# neuron_v3.net
KiCad netlist of a schematic drawn in EAGLE
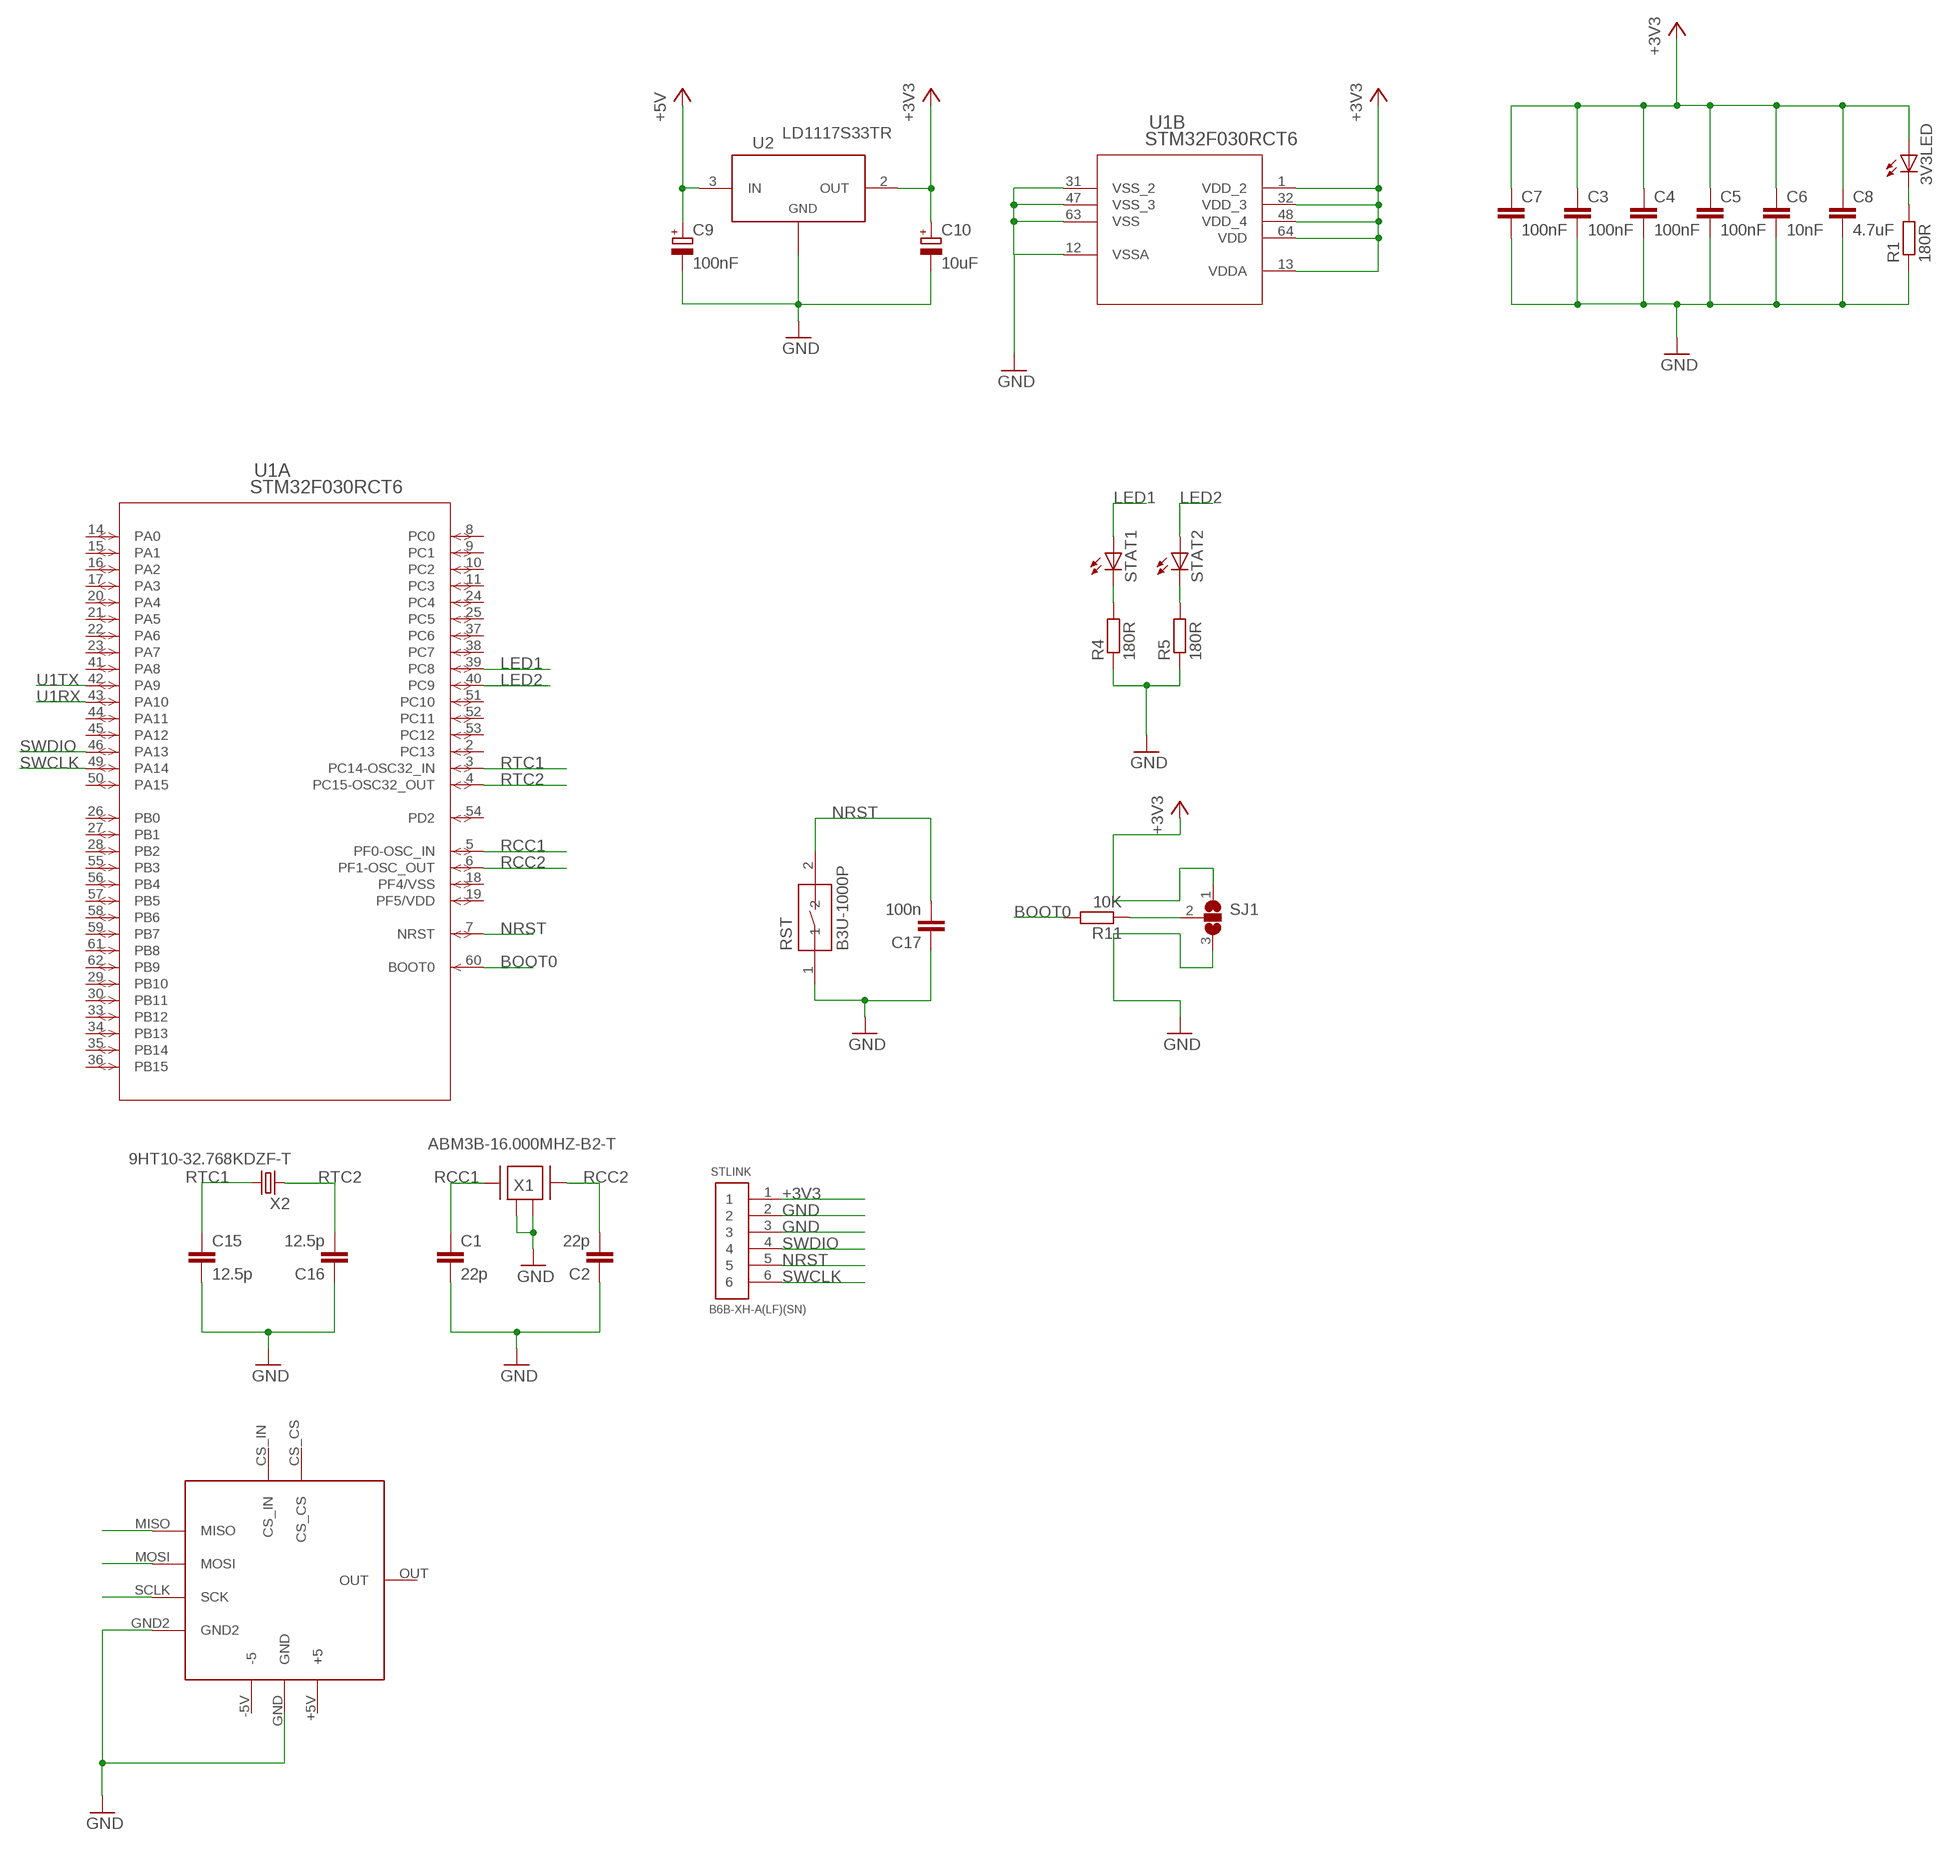
[diagram p0: schematic, sheet 1]

(export (version "E")
  (design (tool "Eeschema 10.0.6"))
  (components
    (comp (ref "3V3LED")
      (value "LEDCHIPLED_0805")
      (footprint "eagle-import:CHIPLED_0805")
      (libsource (lib "eagle-import") (part "LEDCHIPLED_0805"))
    )
    (comp (ref "C1")
      (value "22p")
      (footprint "eagle-import:C0603K")
      (libsource (lib "eagle-import") (part "C-EUC0603K"))
    )
    (comp (ref "C2")
      (value "22p")
      (footprint "eagle-import:C0603K")
      (libsource (lib "eagle-import") (part "C-EUC0603K"))
    )
    (comp (ref "C3")
      (value "100nF")
      (footprint "eagle-import:C0603K")
      (libsource (lib "eagle-import") (part "C-EUC0603K"))
    )
    (comp (ref "C4")
      (value "100nF")
      (footprint "eagle-import:C0603K")
      (libsource (lib "eagle-import") (part "C-EUC0603K"))
    )
    (comp (ref "C5")
      (value "100nF")
      (footprint "eagle-import:C0603K")
      (libsource (lib "eagle-import") (part "C-EUC0603K"))
    )
    (comp (ref "C6")
      (value "10nF")
      (footprint "eagle-import:C0603K")
      (libsource (lib "eagle-import") (part "C-EUC0603K"))
    )
    (comp (ref "C7")
      (value "100nF")
      (footprint "eagle-import:C0603K")
      (libsource (lib "eagle-import") (part "C-EUC0603K"))
    )
    (comp (ref "C8")
      (value "4.7uF")
      (footprint "eagle-import:C0603K")
      (libsource (lib "eagle-import") (part "C-EUC0603K"))
    )
    (comp (ref "C9")
      (value "100nF")
      (footprint "eagle-import:A_3216-18W")
      (libsource (lib "eagle-import") (part "CPOL-EUA/3216-18W"))
    )
    (comp (ref "C10")
      (value "10uF")
      (footprint "eagle-import:A_3216-18W")
      (libsource (lib "eagle-import") (part "CPOL-EUA/3216-18W"))
    )
    (comp (ref "C15")
      (value "12.5p")
      (footprint "eagle-import:C0603K")
      (libsource (lib "eagle-import") (part "C-EUC0603K"))
    )
    (comp (ref "C16")
      (value "12.5p")
      (footprint "eagle-import:C0603K")
      (libsource (lib "eagle-import") (part "C-EUC0603K"))
    )
    (comp (ref "C17")
      (value "100n")
      (footprint "eagle-import:C0603K")
      (libsource (lib "eagle-import") (part "C-EUC0603K"))
    )
    (comp (ref "R1")
      (value "180R")
      (footprint "eagle-import:R0603")
      (libsource (lib "eagle-import") (part "R-EU_R0603"))
    )
    (comp (ref "R4")
      (value "180R")
      (footprint "eagle-import:R0603")
      (libsource (lib "eagle-import") (part "R-EU_R0603"))
    )
    (comp (ref "R5")
      (value "180R")
      (footprint "eagle-import:R0603")
      (libsource (lib "eagle-import") (part "R-EU_R0603"))
    )
    (comp (ref "R11")
      (value "10K")
      (footprint "eagle-import:R0603")
      (libsource (lib "eagle-import") (part "R-EU_R0603"))
    )
    (comp (ref "RST")
      (value "B3U-1000P")
      (footprint "eagle-import:B3U-1000P")
      (fields
        (field (name "DIGI_KEY_PART_NUMBER") "SW1020CT-ND")
        (field (name "MANUFACTURER") "Omron Electronics Inc-EMC Div")
        (field (name "CREATED_BY") "PCBLayout.com")
      )
      (libsource (lib "eagle-import") (part "B3U-1000P"))
    )
    (comp (ref "SJ1")
      (value "SJ2W")
      (footprint "eagle-import:SJ_2")
      (libsource (lib "eagle-import") (part "SJ2W"))
    )
    (comp (ref "STAT1")
      (value "LEDCHIPLED_0805")
      (footprint "eagle-import:CHIPLED_0805")
      (libsource (lib "eagle-import") (part "LEDCHIPLED_0805"))
    )
    (comp (ref "STAT2")
      (value "LEDCHIPLED_0805")
      (footprint "eagle-import:CHIPLED_0805")
      (libsource (lib "eagle-import") (part "LEDCHIPLED_0805"))
    )
    (comp (ref "STLINK")
      (value "B6B-XH-A(LF)(SN)")
      (footprint "eagle-import:B6B-XH-A(LF)(SN)")
      (fields
        (field (name "DIGIKEY_PARTNO") "455-2271-ND")
        (field (name "MANUFACTURER") "JST Sales America Inc.")
        (field (name "CREATED_BY") "PCBLayout.com")
      )
      (libsource (lib "eagle-import") (part "B6B-XH-A(LF)(SN)"))
    )
    (comp (ref "U$1")
      (value "NEURON_BOARD")
      (footprint "eagle-import:NEURON_BOARD")
      (libsource (lib "eagle-import") (part "NEURON_BOARD"))
    )
    (comp (ref "U1")
      (value "STM32F030RCT6")
      (footprint "eagle-import:LQFP64-10X10MM")
      (fields (field (name "COPYRIGHT") "Copyright (C) 2018 Accelerated Designs. All rights reserved"))
      (libsource (lib "eagle-import") (part "STM32F030RCT6"))
    )
    (comp (ref "U2")
      (value "LD1117S33TR")
      (footprint "eagle-import:SOT-223")
      (fields
        (field (name "DIGIKEY_PART_NUMBER") "497-1242-2-ND")
        (field (name "MANUFACTURER") "STMicroelectronics")
        (field (name "CREATED_BY") "PCBLayout.com")
      )
      (libsource (lib "eagle-import") (part "LD1117S33TR"))
    )
    (comp (ref "X1")
      (value "ABM3B-16.000MHZ-B2-T")
      (footprint "eagle-import:ABM3B-16.000MHZ-B2-T")
      (fields
        (field (name "DIGIKEY_PART_NUMBER") "535-9122-2-ND")
        (field (name "MANUFACTURER") "Abracon LLC")
        (field (name "CREATED_BY") "PCBLayout.com")
      )
      (libsource (lib "eagle-import") (part "ABM3B-16.000MHZ-B2-T"))
    )
    (comp (ref "X2")
      (value "9HT10-32.768KDZF-T")
      (footprint "eagle-import:9HT10-32.768KDZF-T")
      (fields
        (field (name "DIGIKEY_PART_NUMBER") "887-1504-2-ND")
        (field (name "MANUFACTURER") "TXC CORPORATION")
        (field (name "CREATED_BY") "PCBLayout.com")
      )
      (libsource (lib "eagle-import") (part "9HT10-32.768KDZF-T"))
    )
  )
  (nets
    (net (code "1") (name "+3V3") (class "Default")
      (node (ref "3V3LED") (pin "A") (pinfunction "A_A") (pintype "passive"))
      (node (ref "C10") (pin "+") (pinfunction "+_+") (pintype "passive"))
      (node (ref "C3") (pin "1") (pinfunction "1_1") (pintype "passive"))
      (node (ref "C4") (pin "1") (pinfunction "1_1") (pintype "passive"))
      (node (ref "C5") (pin "1") (pinfunction "1_1") (pintype "passive"))
      (node (ref "C6") (pin "1") (pinfunction "1_1") (pintype "passive"))
      (node (ref "C7") (pin "1") (pinfunction "1_1") (pintype "passive"))
      (node (ref "C8") (pin "1") (pinfunction "1_1") (pintype "passive"))
      (node (ref "SJ1") (pin "1") (pinfunction "1_1") (pintype "passive"))
      (node (ref "STLINK") (pin "1") (pinfunction "1_1") (pintype "passive"))
      (node (ref "U1") (pin "1") (pinfunction "VDD_2_1") (pintype "power_in"))
      (node (ref "U1") (pin "13") (pinfunction "VDDA_13") (pintype "power_in"))
      (node (ref "U1") (pin "32") (pinfunction "VDD_3_32") (pintype "power_in"))
      (node (ref "U1") (pin "48") (pinfunction "VDD_4_48") (pintype "power_in"))
      (node (ref "U1") (pin "64") (pinfunction "VDD_64") (pintype "power_in"))
      (node (ref "U2") (pin "2") (pinfunction "OUT_2") (pintype "output"))
      (node (ref "U2") (pin "4") (pinfunction "4_4") (pintype "passive"))
    )
    (net (code "2") (name "+5V") (class "Default")
      (node (ref "C9") (pin "+") (pinfunction "+_+") (pintype "passive"))
      (node (ref "U2") (pin "3") (pinfunction "IN_3") (pintype "input"))
    )
    (net (code "3") (name "/BOOT0") (class "Default")
      (node (ref "R11") (pin "2") (pinfunction "2_2") (pintype "passive"))
      (node (ref "U1") (pin "60") (pinfunction "BOOT0_60") (pintype "input"))
    )
    (net (code "4") (name "/LED1") (class "Default")
      (node (ref "STAT1") (pin "A") (pinfunction "A_A") (pintype "passive"))
      (node (ref "U1") (pin "39") (pinfunction "PC8_39") (pintype "bidirectional"))
    )
    (net (code "5") (name "/LED2") (class "Default")
      (node (ref "STAT2") (pin "A") (pinfunction "A_A") (pintype "passive"))
      (node (ref "U1") (pin "40") (pinfunction "PC9_40") (pintype "bidirectional"))
    )
    (net (code "6") (name "/NRST") (class "Default")
      (node (ref "C17") (pin "2") (pinfunction "2_2") (pintype "passive"))
      (node (ref "RST") (pin "2") (pinfunction "2_2") (pintype "passive"))
      (node (ref "STLINK") (pin "5") (pinfunction "5_5") (pintype "passive"))
      (node (ref "U1") (pin "7") (pinfunction "NRST_7") (pintype "bidirectional"))
    )
    (net (code "7") (name "/RCC1") (class "Default")
      (node (ref "C1") (pin "1") (pinfunction "1_1") (pintype "passive"))
      (node (ref "U1") (pin "5") (pinfunction "PF0-OSC_IN_5") (pintype "bidirectional"))
      (node (ref "X1") (pin "1") (pinfunction "1_1") (pintype "passive"))
    )
    (net (code "8") (name "/RCC2") (class "Default")
      (node (ref "C2") (pin "2") (pinfunction "2_2") (pintype "passive"))
      (node (ref "U1") (pin "6") (pinfunction "PF1-OSC_OUT_6") (pintype "bidirectional"))
      (node (ref "X1") (pin "3") (pinfunction "3_3") (pintype "passive"))
    )
    (net (code "9") (name "/RTC1") (class "Default")
      (node (ref "C15") (pin "1") (pinfunction "1_1") (pintype "passive"))
      (node (ref "U1") (pin "3") (pinfunction "PC14-OSC32_IN_3") (pintype "bidirectional"))
      (node (ref "X2") (pin "2") (pinfunction "2_2") (pintype "passive"))
    )
    (net (code "10") (name "/RTC2") (class "Default")
      (node (ref "C16") (pin "2") (pinfunction "2_2") (pintype "passive"))
      (node (ref "U1") (pin "4") (pinfunction "PC15-OSC32_OUT_4") (pintype "bidirectional"))
      (node (ref "X2") (pin "1") (pinfunction "1_1") (pintype "passive"))
    )
    (net (code "11") (name "/SWCLK") (class "Default")
      (node (ref "STLINK") (pin "6") (pinfunction "6_6") (pintype "passive"))
      (node (ref "U1") (pin "49") (pinfunction "PA14_49") (pintype "bidirectional"))
    )
    (net (code "12") (name "/SWDIO") (class "Default")
      (node (ref "STLINK") (pin "4") (pinfunction "4_4") (pintype "passive"))
      (node (ref "U1") (pin "46") (pinfunction "PA13_46") (pintype "bidirectional"))
    )
    (net (code "13") (name "/U1RX") (class "Default")
      (node (ref "U1") (pin "43") (pinfunction "PA10_43") (pintype "bidirectional"))
    )
    (net (code "14") (name "/U1TX") (class "Default")
      (node (ref "U1") (pin "42") (pinfunction "PA9_42") (pintype "bidirectional"))
    )
    (net (code "15") (name "GND") (class "Default")
      (node (ref "C1") (pin "2") (pinfunction "2_2") (pintype "passive"))
      (node (ref "C10") (pin "-") (pinfunction "-_-") (pintype "passive"))
      (node (ref "C15") (pin "2") (pinfunction "2_2") (pintype "passive"))
      (node (ref "C16") (pin "1") (pinfunction "1_1") (pintype "passive"))
      (node (ref "C17") (pin "1") (pinfunction "1_1") (pintype "passive"))
      (node (ref "C2") (pin "1") (pinfunction "1_1") (pintype "passive"))
      (node (ref "C3") (pin "2") (pinfunction "2_2") (pintype "passive"))
      (node (ref "C4") (pin "2") (pinfunction "2_2") (pintype "passive"))
      (node (ref "C5") (pin "2") (pinfunction "2_2") (pintype "passive"))
      (node (ref "C6") (pin "2") (pinfunction "2_2") (pintype "passive"))
      (node (ref "C7") (pin "2") (pinfunction "2_2") (pintype "passive"))
      (node (ref "C8") (pin "2") (pinfunction "2_2") (pintype "passive"))
      (node (ref "C9") (pin "-") (pinfunction "-_-") (pintype "passive"))
      (node (ref "R1") (pin "1") (pinfunction "1_1") (pintype "passive"))
      (node (ref "R4") (pin "1") (pinfunction "1_1") (pintype "passive"))
      (node (ref "R5") (pin "1") (pinfunction "1_1") (pintype "passive"))
      (node (ref "RST") (pin "1") (pinfunction "1_1") (pintype "passive"))
      (node (ref "SJ1") (pin "3") (pinfunction "3_3") (pintype "passive"))
      (node (ref "STLINK") (pin "2") (pinfunction "2_2") (pintype "passive"))
      (node (ref "STLINK") (pin "3") (pinfunction "3_3") (pintype "passive"))
      (node (ref "U$1") (pin "GND") (pinfunction "GND_GND") (pintype "bidirectional"))
      (node (ref "U$1") (pin "GND2") (pinfunction "GND2_GND2") (pintype "bidirectional"))
      (node (ref "U1") (pin "12") (pinfunction "VSSA_12") (pintype "power_in"))
      (node (ref "U1") (pin "31") (pinfunction "VSS_2_31") (pintype "power_in"))
      (node (ref "U1") (pin "47") (pinfunction "VSS_3_47") (pintype "power_in"))
      (node (ref "U1") (pin "63") (pinfunction "VSS_63") (pintype "power_in"))
      (node (ref "U2") (pin "1") (pinfunction "ADJ/GND_1") (pintype "power_in"))
      (node (ref "X1") (pin "2") (pinfunction "2_2") (pintype "passive"))
      (node (ref "X1") (pin "4") (pinfunction "4_4") (pintype "passive"))
    )
    (net (code "16") (name "Net-(3V3LED-PadC)") (class "Default")
      (node (ref "3V3LED") (pin "C") (pinfunction "C_C") (pintype "passive"))
      (node (ref "R1") (pin "2") (pinfunction "2_2") (pintype "passive"))
    )
    (net (code "17") (name "Net-(R4-Pad2)") (class "Default")
      (node (ref "R4") (pin "2") (pinfunction "2_2") (pintype "passive"))
      (node (ref "STAT1") (pin "C") (pinfunction "C_C") (pintype "passive"))
    )
    (net (code "18") (name "Net-(R5-Pad2)") (class "Default")
      (node (ref "R5") (pin "2") (pinfunction "2_2") (pintype "passive"))
      (node (ref "STAT2") (pin "C") (pinfunction "C_C") (pintype "passive"))
    )
    (net (code "19") (name "Net-(R11-Pad1)") (class "Default")
      (node (ref "R11") (pin "1") (pinfunction "1_1") (pintype "passive"))
      (node (ref "SJ1") (pin "2") (pinfunction "2_2") (pintype "passive"))
    )
    (net (code "20") (name "unconnected-(U$1-+5-Pad+5V)") (class "Default")
      (node (ref "U$1") (pin "+5V") (pinfunction "+5_+5V") (pintype "bidirectional"))
    )
    (net (code "21") (name "unconnected-(U$1--5-Pad-5V)") (class "Default")
      (node (ref "U$1") (pin "-5V") (pinfunction "-5_-5V") (pintype "bidirectional"))
    )
    (net (code "22") (name "unconnected-(U$1-PadCS_CS)") (class "Default")
      (node (ref "U$1") (pin "CS_CS") (pinfunction "CS_CS_CS_CS") (pintype "bidirectional"))
    )
    (net (code "23") (name "unconnected-(U$1-PadCS_IN)") (class "Default")
      (node (ref "U$1") (pin "CS_IN") (pinfunction "CS_IN_CS_IN") (pintype "bidirectional"))
    )
    (net (code "24") (name "unconnected-(U$1-PadMISO)") (class "Default")
      (node (ref "U$1") (pin "MISO") (pinfunction "MISO_MISO") (pintype "bidirectional"))
    )
    (net (code "25") (name "unconnected-(U$1-PadMOSI)") (class "Default")
      (node (ref "U$1") (pin "MOSI") (pinfunction "MOSI_MOSI") (pintype "bidirectional"))
    )
    (net (code "26") (name "unconnected-(U$1-PadOUT)") (class "Default")
      (node (ref "U$1") (pin "OUT") (pinfunction "OUT_OUT") (pintype "bidirectional"))
    )
    (net (code "27") (name "unconnected-(U$1-SCK-PadSCLK)") (class "Default")
      (node (ref "U$1") (pin "SCLK") (pinfunction "SCK_SCLK") (pintype "bidirectional"))
    )
    (net (code "28") (name "unconnected-(U1A-PA0-Pad14)") (class "Default")
      (node (ref "U1") (pin "14") (pinfunction "PA0_14") (pintype "bidirectional"))
    )
    (net (code "29") (name "unconnected-(U1A-PA1-Pad15)") (class "Default")
      (node (ref "U1") (pin "15") (pinfunction "PA1_15") (pintype "bidirectional"))
    )
    (net (code "30") (name "unconnected-(U1A-PA2-Pad16)") (class "Default")
      (node (ref "U1") (pin "16") (pinfunction "PA2_16") (pintype "bidirectional"))
    )
    (net (code "31") (name "unconnected-(U1A-PA3-Pad17)") (class "Default")
      (node (ref "U1") (pin "17") (pinfunction "PA3_17") (pintype "bidirectional"))
    )
    (net (code "32") (name "unconnected-(U1A-PA4-Pad20)") (class "Default")
      (node (ref "U1") (pin "20") (pinfunction "PA4_20") (pintype "bidirectional"))
    )
    (net (code "33") (name "unconnected-(U1A-PA5-Pad21)") (class "Default")
      (node (ref "U1") (pin "21") (pinfunction "PA5_21") (pintype "bidirectional"))
    )
    (net (code "34") (name "unconnected-(U1A-PA6-Pad22)") (class "Default")
      (node (ref "U1") (pin "22") (pinfunction "PA6_22") (pintype "bidirectional"))
    )
    (net (code "35") (name "unconnected-(U1A-PA7-Pad23)") (class "Default")
      (node (ref "U1") (pin "23") (pinfunction "PA7_23") (pintype "bidirectional"))
    )
    (net (code "36") (name "unconnected-(U1A-PA8-Pad41)") (class "Default")
      (node (ref "U1") (pin "41") (pinfunction "PA8_41") (pintype "bidirectional"))
    )
    (net (code "37") (name "unconnected-(U1A-PA11-Pad44)") (class "Default")
      (node (ref "U1") (pin "44") (pinfunction "PA11_44") (pintype "bidirectional"))
    )
    (net (code "38") (name "unconnected-(U1A-PA12-Pad45)") (class "Default")
      (node (ref "U1") (pin "45") (pinfunction "PA12_45") (pintype "bidirectional"))
    )
    (net (code "39") (name "unconnected-(U1A-PA15-Pad50)") (class "Default")
      (node (ref "U1") (pin "50") (pinfunction "PA15_50") (pintype "bidirectional"))
    )
    (net (code "40") (name "unconnected-(U1A-PB0-Pad26)") (class "Default")
      (node (ref "U1") (pin "26") (pinfunction "PB0_26") (pintype "bidirectional"))
    )
    (net (code "41") (name "unconnected-(U1A-PB1-Pad27)") (class "Default")
      (node (ref "U1") (pin "27") (pinfunction "PB1_27") (pintype "bidirectional"))
    )
    (net (code "42") (name "unconnected-(U1A-PB2-Pad28)") (class "Default")
      (node (ref "U1") (pin "28") (pinfunction "PB2_28") (pintype "bidirectional"))
    )
    (net (code "43") (name "unconnected-(U1A-PB3-Pad55)") (class "Default")
      (node (ref "U1") (pin "55") (pinfunction "PB3_55") (pintype "bidirectional"))
    )
    (net (code "44") (name "unconnected-(U1A-PB4-Pad56)") (class "Default")
      (node (ref "U1") (pin "56") (pinfunction "PB4_56") (pintype "bidirectional"))
    )
    (net (code "45") (name "unconnected-(U1A-PB5-Pad57)") (class "Default")
      (node (ref "U1") (pin "57") (pinfunction "PB5_57") (pintype "bidirectional"))
    )
    (net (code "46") (name "unconnected-(U1A-PB6-Pad58)") (class "Default")
      (node (ref "U1") (pin "58") (pinfunction "PB6_58") (pintype "bidirectional"))
    )
    (net (code "47") (name "unconnected-(U1A-PB7-Pad59)") (class "Default")
      (node (ref "U1") (pin "59") (pinfunction "PB7_59") (pintype "bidirectional"))
    )
    (net (code "48") (name "unconnected-(U1A-PB8-Pad61)") (class "Default")
      (node (ref "U1") (pin "61") (pinfunction "PB8_61") (pintype "bidirectional"))
    )
    (net (code "49") (name "unconnected-(U1A-PB9-Pad62)") (class "Default")
      (node (ref "U1") (pin "62") (pinfunction "PB9_62") (pintype "bidirectional"))
    )
    (net (code "50") (name "unconnected-(U1A-PB10-Pad29)") (class "Default")
      (node (ref "U1") (pin "29") (pinfunction "PB10_29") (pintype "bidirectional"))
    )
    (net (code "51") (name "unconnected-(U1A-PB11-Pad30)") (class "Default")
      (node (ref "U1") (pin "30") (pinfunction "PB11_30") (pintype "bidirectional"))
    )
    (net (code "52") (name "unconnected-(U1A-PB12-Pad33)") (class "Default")
      (node (ref "U1") (pin "33") (pinfunction "PB12_33") (pintype "bidirectional"))
    )
    (net (code "53") (name "unconnected-(U1A-PB13-Pad34)") (class "Default")
      (node (ref "U1") (pin "34") (pinfunction "PB13_34") (pintype "bidirectional"))
    )
    (net (code "54") (name "unconnected-(U1A-PB14-Pad35)") (class "Default")
      (node (ref "U1") (pin "35") (pinfunction "PB14_35") (pintype "bidirectional"))
    )
    (net (code "55") (name "unconnected-(U1A-PB15-Pad36)") (class "Default")
      (node (ref "U1") (pin "36") (pinfunction "PB15_36") (pintype "bidirectional"))
    )
    (net (code "56") (name "unconnected-(U1A-PC0-Pad8)") (class "Default")
      (node (ref "U1") (pin "8") (pinfunction "PC0_8") (pintype "bidirectional"))
    )
    (net (code "57") (name "unconnected-(U1A-PC1-Pad9)") (class "Default")
      (node (ref "U1") (pin "9") (pinfunction "PC1_9") (pintype "bidirectional"))
    )
    (net (code "58") (name "unconnected-(U1A-PC2-Pad10)") (class "Default")
      (node (ref "U1") (pin "10") (pinfunction "PC2_10") (pintype "bidirectional"))
    )
    (net (code "59") (name "unconnected-(U1A-PC3-Pad11)") (class "Default")
      (node (ref "U1") (pin "11") (pinfunction "PC3_11") (pintype "bidirectional"))
    )
    (net (code "60") (name "unconnected-(U1A-PC4-Pad24)") (class "Default")
      (node (ref "U1") (pin "24") (pinfunction "PC4_24") (pintype "bidirectional"))
    )
    (net (code "61") (name "unconnected-(U1A-PC5-Pad25)") (class "Default")
      (node (ref "U1") (pin "25") (pinfunction "PC5_25") (pintype "bidirectional"))
    )
    (net (code "62") (name "unconnected-(U1A-PC6-Pad37)") (class "Default")
      (node (ref "U1") (pin "37") (pinfunction "PC6_37") (pintype "bidirectional"))
    )
    (net (code "63") (name "unconnected-(U1A-PC7-Pad38)") (class "Default")
      (node (ref "U1") (pin "38") (pinfunction "PC7_38") (pintype "bidirectional"))
    )
    (net (code "64") (name "unconnected-(U1A-PC10-Pad51)") (class "Default")
      (node (ref "U1") (pin "51") (pinfunction "PC10_51") (pintype "bidirectional"))
    )
    (net (code "65") (name "unconnected-(U1A-PC11-Pad52)") (class "Default")
      (node (ref "U1") (pin "52") (pinfunction "PC11_52") (pintype "bidirectional"))
    )
    (net (code "66") (name "unconnected-(U1A-PC12-Pad53)") (class "Default")
      (node (ref "U1") (pin "53") (pinfunction "PC12_53") (pintype "bidirectional"))
    )
    (net (code "67") (name "unconnected-(U1A-PC13-Pad2)") (class "Default")
      (node (ref "U1") (pin "2") (pinfunction "PC13_2") (pintype "bidirectional"))
    )
    (net (code "68") (name "unconnected-(U1A-PD2-Pad54)") (class "Default")
      (node (ref "U1") (pin "54") (pinfunction "PD2_54") (pintype "bidirectional"))
    )
    (net (code "69") (name "unconnected-(U1A-PF4{slash}VSS-Pad18)") (class "Default")
      (node (ref "U1") (pin "18") (pinfunction "PF4/VSS_18") (pintype "bidirectional"))
    )
    (net (code "70") (name "unconnected-(U1A-PF5{slash}VDD-Pad19)") (class "Default")
      (node (ref "U1") (pin "19") (pinfunction "PF5/VDD_19") (pintype "bidirectional"))
    )
  )
)
